# fpga_io_bank_2_fmc.net
KiCad netlist of a schematic drawn in Altium Designer
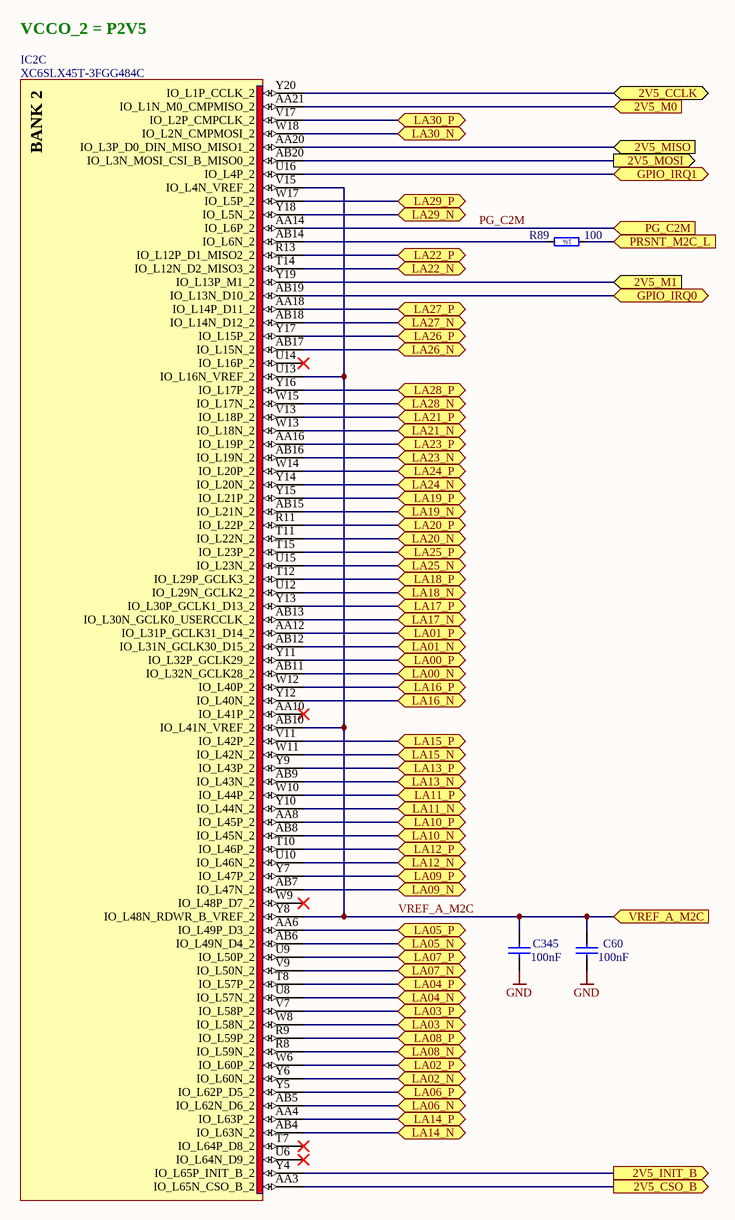
[diagram p0: fpga_io_bank_2_fmc.SchDoc]

(export (version "E")
  (design (tool "Eeschema 10.0.6"))
  (components
    (comp (ref "C60")
      (value "100nF")
      (footprint "CAPC1005X55N")
      (description "Non-polarised capacitor")
      (fields
        (field (name "PART NUMBER") "CC0402_100NF_16V_10%_X7R")
        (field (name "VOLTAGE") "16V")
        (field (name "AUTHOR") "CERN DEM JLC")
      )
      (libsource (lib "Capacitors") (part "Capacitor - non polarized"))
    )
    (comp (ref "C345")
      (value "100nF")
      (footprint "CAPC1005X55N")
      (description "Non-polarised capacitor")
      (fields
        (field (name "PART NUMBER") "CC0402_100NF_16V_10%_X7R")
        (field (name "VOLTAGE") "16V")
        (field (name "AUTHOR") "CERN DEM JLC")
      )
      (libsource (lib "Capacitors") (part "Capacitor - non polarized"))
    )
    (comp (ref "IC2")
      (value "XC6SLX45T-3FGG484C")
      (footprint "BGA484C100P22X22_2300X2300X260")
      (fields (field (name "MANUFACTURER") "XILINX") (field (name "AUTHOR") "CERN DEM JLC"))
      (libsource (lib "ICs And Semiconductors") (part "XC6SLX45T-3FGG484C"))
    )
    (comp (ref "R89")
      (value "100")
      (footprint "RESC1608X55N")
      (description "Resistor - 1%")
      (fields
        (field (name "PART NUMBER") "R0603_100R_1%_0.1W_100PPM")
        (field (name "POWER") "0.1W")
        (field (name "AUTHOR") "CERN DEM JLC")
      )
      (libsource (lib "Resistors") (part "Resistor - 1%"))
    )
  )
  (nets
    (net (code "1") (name "/2V5_CCLK") (class "Default")
      (node (ref "IC2") (pin "Y20") (pinfunction "IO_L1P_CCLK_2_Y20") (pintype "bidirectional"))
    )
    (net (code "2") (name "/2V5_CSO_B") (class "Default")
      (node (ref "IC2") (pin "AA3") (pinfunction "IO_L65N_CSO_B_2_AA3") (pintype "bidirectional"))
    )
    (net (code "3") (name "/2V5_INIT_B") (class "Default")
      (node (ref "IC2") (pin "Y4") (pinfunction "IO_L65P_INIT_B_2_Y4") (pintype "bidirectional"))
    )
    (net (code "4") (name "/2V5_M0") (class "Default")
      (node (ref "IC2") (pin "AA21") (pinfunction "IO_L1N_M0_CMPMISO_2_AA21") (pintype "bidirectional"))
    )
    (net (code "5") (name "/2V5_M1") (class "Default")
      (node (ref "IC2") (pin "Y19") (pinfunction "IO_L13P_M1_2_Y19") (pintype "bidirectional"))
    )
    (net (code "6") (name "/2V5_MISO") (class "Default")
      (node (ref "IC2") (pin "AA20") (pinfunction "IO_L3P_D0_DIN_MISO_MISO1_2_AA20") (pintype "bidirectional"))
    )
    (net (code "7") (name "/2V5_MOSI") (class "Default")
      (node (ref "IC2") (pin "AB20") (pinfunction "IO_L3N_MOSI_CSI_B_MISO0_2_AB20") (pintype "bidirectional"))
    )
    (net (code "8") (name "/GPIO_IRQ0") (class "Default")
      (node (ref "IC2") (pin "AB19") (pinfunction "IO_L13N_D10_2_AB19") (pintype "bidirectional"))
    )
    (net (code "9") (name "/GPIO_IRQ1") (class "Default")
      (node (ref "IC2") (pin "U16") (pinfunction "IO_L4P_2_U16") (pintype "bidirectional"))
    )
    (net (code "10") (name "/LA00_N") (class "Default")
      (node (ref "IC2") (pin "AB11") (pinfunction "IO_L32N_GCLK28_2_AB11") (pintype "bidirectional"))
    )
    (net (code "11") (name "/LA00_P") (class "Default")
      (node (ref "IC2") (pin "Y11") (pinfunction "IO_L32P_GCLK29_2_Y11") (pintype "bidirectional"))
    )
    (net (code "12") (name "/LA01_N") (class "Default")
      (node (ref "IC2") (pin "AB12") (pinfunction "IO_L31N_GCLK30_D15_2_AB12") (pintype "bidirectional"))
    )
    (net (code "13") (name "/LA01_P") (class "Default")
      (node (ref "IC2") (pin "AA12") (pinfunction "IO_L31P_GCLK31_D14_2_AA12") (pintype "bidirectional"))
    )
    (net (code "14") (name "/LA02_N") (class "Default")
      (node (ref "IC2") (pin "Y6") (pinfunction "IO_L60N_2_Y6") (pintype "bidirectional"))
    )
    (net (code "15") (name "/LA02_P") (class "Default")
      (node (ref "IC2") (pin "W6") (pinfunction "IO_L60P_2_W6") (pintype "bidirectional"))
    )
    (net (code "16") (name "/LA03_N") (class "Default")
      (node (ref "IC2") (pin "W8") (pinfunction "IO_L58N_2_W8") (pintype "bidirectional"))
    )
    (net (code "17") (name "/LA03_P") (class "Default")
      (node (ref "IC2") (pin "V7") (pinfunction "IO_L58P_2_V7") (pintype "bidirectional"))
    )
    (net (code "18") (name "/LA04_N") (class "Default")
      (node (ref "IC2") (pin "U8") (pinfunction "IO_L57N_2_U8") (pintype "bidirectional"))
    )
    (net (code "19") (name "/LA04_P") (class "Default")
      (node (ref "IC2") (pin "T8") (pinfunction "IO_L57P_2_T8") (pintype "bidirectional"))
    )
    (net (code "20") (name "/LA05_N") (class "Default")
      (node (ref "IC2") (pin "AB6") (pinfunction "IO_L49N_D4_2_AB6") (pintype "bidirectional"))
    )
    (net (code "21") (name "/LA05_P") (class "Default")
      (node (ref "IC2") (pin "AA6") (pinfunction "IO_L49P_D3_2_AA6") (pintype "bidirectional"))
    )
    (net (code "22") (name "/LA06_N") (class "Default")
      (node (ref "IC2") (pin "AB5") (pinfunction "IO_L62N_D6_2_AB5") (pintype "bidirectional"))
    )
    (net (code "23") (name "/LA06_P") (class "Default")
      (node (ref "IC2") (pin "Y5") (pinfunction "IO_L62P_D5_2_Y5") (pintype "bidirectional"))
    )
    (net (code "24") (name "/LA07_N") (class "Default")
      (node (ref "IC2") (pin "V9") (pinfunction "IO_L50N_2_V9") (pintype "bidirectional"))
    )
    (net (code "25") (name "/LA07_P") (class "Default")
      (node (ref "IC2") (pin "U9") (pinfunction "IO_L50P_2_U9") (pintype "bidirectional"))
    )
    (net (code "26") (name "/LA08_N") (class "Default")
      (node (ref "IC2") (pin "R8") (pinfunction "IO_L59N_2_R8") (pintype "bidirectional"))
    )
    (net (code "27") (name "/LA08_P") (class "Default")
      (node (ref "IC2") (pin "R9") (pinfunction "IO_L59P_2_R9") (pintype "bidirectional"))
    )
    (net (code "28") (name "/LA09_N") (class "Default")
      (node (ref "IC2") (pin "AB7") (pinfunction "IO_L47N_2_AB7") (pintype "bidirectional"))
    )
    (net (code "29") (name "/LA09_P") (class "Default")
      (node (ref "IC2") (pin "Y7") (pinfunction "IO_L47P_2_Y7") (pintype "bidirectional"))
    )
    (net (code "30") (name "/LA10_N") (class "Default")
      (node (ref "IC2") (pin "AB8") (pinfunction "IO_L45N_2_AB8") (pintype "bidirectional"))
    )
    (net (code "31") (name "/LA10_P") (class "Default")
      (node (ref "IC2") (pin "AA8") (pinfunction "IO_L45P_2_AA8") (pintype "bidirectional"))
    )
    (net (code "32") (name "/LA11_N") (class "Default")
      (node (ref "IC2") (pin "Y10") (pinfunction "IO_L44N_2_Y10") (pintype "bidirectional"))
    )
    (net (code "33") (name "/LA11_P") (class "Default")
      (node (ref "IC2") (pin "W10") (pinfunction "IO_L44P_2_W10") (pintype "bidirectional"))
    )
    (net (code "34") (name "/LA12_N") (class "Default")
      (node (ref "IC2") (pin "U10") (pinfunction "IO_L46N_2_U10") (pintype "bidirectional"))
    )
    (net (code "35") (name "/LA12_P") (class "Default")
      (node (ref "IC2") (pin "T10") (pinfunction "IO_L46P_2_T10") (pintype "bidirectional"))
    )
    (net (code "36") (name "/LA13_N") (class "Default")
      (node (ref "IC2") (pin "AB9") (pinfunction "IO_L43N_2_AB9") (pintype "bidirectional"))
    )
    (net (code "37") (name "/LA13_P") (class "Default")
      (node (ref "IC2") (pin "Y9") (pinfunction "IO_L43P_2_Y9") (pintype "bidirectional"))
    )
    (net (code "38") (name "/LA14_N") (class "Default")
      (node (ref "IC2") (pin "AB4") (pinfunction "IO_L63N_2_AB4") (pintype "bidirectional"))
    )
    (net (code "39") (name "/LA14_P") (class "Default")
      (node (ref "IC2") (pin "AA4") (pinfunction "IO_L63P_2_AA4") (pintype "bidirectional"))
    )
    (net (code "40") (name "/LA15_N") (class "Default")
      (node (ref "IC2") (pin "W11") (pinfunction "IO_L42N_2_W11") (pintype "bidirectional"))
    )
    (net (code "41") (name "/LA15_P") (class "Default")
      (node (ref "IC2") (pin "V11") (pinfunction "IO_L42P_2_V11") (pintype "bidirectional"))
    )
    (net (code "42") (name "/LA16_N") (class "Default")
      (node (ref "IC2") (pin "Y12") (pinfunction "IO_L40N_2_Y12") (pintype "bidirectional"))
    )
    (net (code "43") (name "/LA16_P") (class "Default")
      (node (ref "IC2") (pin "W12") (pinfunction "IO_L40P_2_W12") (pintype "bidirectional"))
    )
    (net (code "44") (name "/LA17_N") (class "Default")
      (node (ref "IC2") (pin "AB13") (pinfunction "IO_L30N_GCLK0_USERCCLK_2_AB13") (pintype "bidirectional"))
    )
    (net (code "45") (name "/LA17_P") (class "Default")
      (node (ref "IC2") (pin "Y13") (pinfunction "IO_L30P_GCLK1_D13_2_Y13") (pintype "bidirectional"))
    )
    (net (code "46") (name "/LA18_N") (class "Default")
      (node (ref "IC2") (pin "U12") (pinfunction "IO_L29N_GCLK2_2_U12") (pintype "bidirectional"))
    )
    (net (code "47") (name "/LA18_P") (class "Default")
      (node (ref "IC2") (pin "T12") (pinfunction "IO_L29P_GCLK3_2_T12") (pintype "bidirectional"))
    )
    (net (code "48") (name "/LA19_N") (class "Default")
      (node (ref "IC2") (pin "AB15") (pinfunction "IO_L21N_2_AB15") (pintype "bidirectional"))
    )
    (net (code "49") (name "/LA19_P") (class "Default")
      (node (ref "IC2") (pin "Y15") (pinfunction "IO_L21P_2_Y15") (pintype "bidirectional"))
    )
    (net (code "50") (name "/LA20_N") (class "Default")
      (node (ref "IC2") (pin "T11") (pinfunction "IO_L22N_2_T11") (pintype "bidirectional"))
    )
    (net (code "51") (name "/LA20_P") (class "Default")
      (node (ref "IC2") (pin "R11") (pinfunction "IO_L22P_2_R11") (pintype "bidirectional"))
    )
    (net (code "52") (name "/LA21_N") (class "Default")
      (node (ref "IC2") (pin "W13") (pinfunction "IO_L18N_2_W13") (pintype "bidirectional"))
    )
    (net (code "53") (name "/LA21_P") (class "Default")
      (node (ref "IC2") (pin "V13") (pinfunction "IO_L18P_2_V13") (pintype "bidirectional"))
    )
    (net (code "54") (name "/LA22_N") (class "Default")
      (node (ref "IC2") (pin "T14") (pinfunction "IO_L12N_D2_MISO3_2_T14") (pintype "bidirectional"))
    )
    (net (code "55") (name "/LA22_P") (class "Default")
      (node (ref "IC2") (pin "R13") (pinfunction "IO_L12P_D1_MISO2_2_R13") (pintype "bidirectional"))
    )
    (net (code "56") (name "/LA23_N") (class "Default")
      (node (ref "IC2") (pin "AB16") (pinfunction "IO_L19N_2_AB16") (pintype "bidirectional"))
    )
    (net (code "57") (name "/LA23_P") (class "Default")
      (node (ref "IC2") (pin "AA16") (pinfunction "IO_L19P_2_AA16") (pintype "bidirectional"))
    )
    (net (code "58") (name "/LA24_N") (class "Default")
      (node (ref "IC2") (pin "Y14") (pinfunction "IO_L20N_2_Y14") (pintype "bidirectional"))
    )
    (net (code "59") (name "/LA24_P") (class "Default")
      (node (ref "IC2") (pin "W14") (pinfunction "IO_L20P_2_W14") (pintype "bidirectional"))
    )
    (net (code "60") (name "/LA25_N") (class "Default")
      (node (ref "IC2") (pin "U15") (pinfunction "IO_L23N_2_U15") (pintype "bidirectional"))
    )
    (net (code "61") (name "/LA25_P") (class "Default")
      (node (ref "IC2") (pin "T15") (pinfunction "IO_L23P_2_T15") (pintype "bidirectional"))
    )
    (net (code "62") (name "/LA26_N") (class "Default")
      (node (ref "IC2") (pin "AB17") (pinfunction "IO_L15N_2_AB17") (pintype "bidirectional"))
    )
    (net (code "63") (name "/LA26_P") (class "Default")
      (node (ref "IC2") (pin "Y17") (pinfunction "IO_L15P_2_Y17") (pintype "bidirectional"))
    )
    (net (code "64") (name "/LA27_N") (class "Default")
      (node (ref "IC2") (pin "AB18") (pinfunction "IO_L14N_D12_2_AB18") (pintype "bidirectional"))
    )
    (net (code "65") (name "/LA27_P") (class "Default")
      (node (ref "IC2") (pin "AA18") (pinfunction "IO_L14P_D11_2_AA18") (pintype "bidirectional"))
    )
    (net (code "66") (name "/LA28_N") (class "Default")
      (node (ref "IC2") (pin "W15") (pinfunction "IO_L17N_2_W15") (pintype "bidirectional"))
    )
    (net (code "67") (name "/LA28_P") (class "Default")
      (node (ref "IC2") (pin "Y16") (pinfunction "IO_L17P_2_Y16") (pintype "bidirectional"))
    )
    (net (code "68") (name "/LA29_N") (class "Default")
      (node (ref "IC2") (pin "Y18") (pinfunction "IO_L5N_2_Y18") (pintype "bidirectional"))
    )
    (net (code "69") (name "/LA29_P") (class "Default")
      (node (ref "IC2") (pin "W17") (pinfunction "IO_L5P_2_W17") (pintype "bidirectional"))
    )
    (net (code "70") (name "/LA30_N") (class "Default")
      (node (ref "IC2") (pin "W18") (pinfunction "IO_L2N_CMPMOSI_2_W18") (pintype "bidirectional"))
    )
    (net (code "71") (name "/LA30_P") (class "Default")
      (node (ref "IC2") (pin "V17") (pinfunction "IO_L2P_CMPCLK_2_V17") (pintype "bidirectional"))
    )
    (net (code "72") (name "/PG_C2M") (class "Default")
      (node (ref "IC2") (pin "AA14") (pinfunction "IO_L6P_2_AA14") (pintype "bidirectional"))
    )
    (net (code "73") (name "/PRSNT_M2C_L") (class "Default")
      (node (ref "R89") (pin "1") (pinfunction "1_1") (pintype "passive"))
    )
    (net (code "74") (name "/VREF_A_M2C") (class "Default")
      (node (ref "C345") (pin "2") (pinfunction "2_2") (pintype "passive"))
      (node (ref "C60") (pin "2") (pinfunction "2_2") (pintype "passive"))
      (node (ref "IC2") (pin "AB10") (pinfunction "IO_L41N_VREF_2_AB10") (pintype "bidirectional"))
      (node (ref "IC2") (pin "U13") (pinfunction "IO_L16N_VREF_2_U13") (pintype "bidirectional"))
      (node (ref "IC2") (pin "V15") (pinfunction "IO_L4N_VREF_2_V15") (pintype "bidirectional"))
      (node (ref "IC2") (pin "Y8") (pinfunction "IO_L48N_RDWR_B_VREF_2_Y8") (pintype "bidirectional"))
    )
    (net (code "75") (name "GND") (class "Default")
      (node (ref "C345") (pin "1") (pinfunction "1_1") (pintype "passive"))
      (node (ref "C60") (pin "1") (pinfunction "1_1") (pintype "passive"))
    )
    (net (code "76") (name "Net-(IC2C-IO_L6N_2)") (class "Default")
      (node (ref "IC2") (pin "AB14") (pinfunction "IO_L6N_2_AB14") (pintype "bidirectional"))
      (node (ref "R89") (pin "2") (pinfunction "2_2") (pintype "passive"))
    )
    (net (code "77") (name "unconnected-(IC2C-IO_L16P_2-PadU14)") (class "Default")
      (node (ref "IC2") (pin "U14") (pinfunction "IO_L16P_2_U14") (pintype "bidirectional+no_connect"))
    )
    (net (code "78") (name "unconnected-(IC2C-IO_L41P_2-PadAA10)") (class "Default")
      (node (ref "IC2") (pin "AA10") (pinfunction "IO_L41P_2_AA10") (pintype "bidirectional+no_connect"))
    )
    (net (code "79") (name "unconnected-(IC2C-IO_L48P_D7_2-PadW9)") (class "Default")
      (node (ref "IC2") (pin "W9") (pinfunction "IO_L48P_D7_2_W9") (pintype "bidirectional+no_connect"))
    )
    (net (code "80") (name "unconnected-(IC2C-IO_L64N_D9_2-PadU6)") (class "Default")
      (node (ref "IC2") (pin "U6") (pinfunction "IO_L64N_D9_2_U6") (pintype "bidirectional+no_connect"))
    )
    (net (code "81") (name "unconnected-(IC2C-IO_L64P_D8_2-PadT7)") (class "Default")
      (node (ref "IC2") (pin "T7") (pinfunction "IO_L64P_D8_2_T7") (pintype "bidirectional+no_connect"))
    )
  )
)
